# M5StickCplusbattery.net
KiCad netlist of a schematic drawn in EAGLE
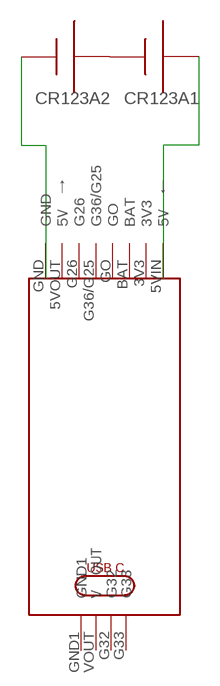
[diagram p0: schematic, sheet 1]

(export (version "E")
  (design (tool "Eeschema 10.0.6"))
  (components
    (comp (ref "CR123A1")
      (value "AAA")
      (footprint "eagle-import:12BH412")
      (libsource (lib "eagle-import") (part "AAA"))
    )
    (comp (ref "CR123A2")
      (value "AAA")
      (footprint "eagle-import:12BH412")
      (libsource (lib "eagle-import") (part "AAA"))
    )
    (comp (ref "U$1")
      (value "M5STICKCPLUS")
      (footprint "eagle-import:M5STICK")
      (libsource (lib "eagle-import") (part "M5STICKCPLUS"))
    )
  )
  (nets
    (net (code "1") (name "Net-(CR123A1-Pad+)") (class "Default")
      (node (ref "CR123A1") (pin "+") (pinfunction "+_+") (pintype "bidirectional"))
      (node (ref "CR123A2") (pin "-") (pinfunction "-_-") (pintype "bidirectional"))
    )
    (net (code "2") (name "Net-(CR123A2-Pad+)") (class "Default")
      (node (ref "CR123A2") (pin "+") (pinfunction "+_+") (pintype "bidirectional"))
      (node (ref "U$1") (pin "GND") (pinfunction "GND_GND") (pintype "bidirectional"))
    )
    (net (code "3") (name "Net-(U$1-5V　←)") (class "Default")
      (node (ref "CR123A1") (pin "-") (pinfunction "-_-") (pintype "bidirectional"))
      (node (ref "U$1") (pin "5VIN") (pinfunction "5V　←_5VIN") (pintype "bidirectional"))
    )
    (net (code "4") (name "unconnected-(U$1-5V　→-Pad5VOUT)") (class "Default")
      (node (ref "U$1") (pin "5VOUT") (pinfunction "5V　→_5VOUT") (pintype "bidirectional"))
    )
    (net (code "5") (name "unconnected-(U$1-Pad3V3)") (class "Default")
      (node (ref "U$1") (pin "3V3") (pinfunction "3V3_3V3") (pintype "bidirectional"))
    )
    (net (code "6") (name "unconnected-(U$1-PadBAT)") (class "Default")
      (node (ref "U$1") (pin "BAT") (pinfunction "BAT_BAT") (pintype "bidirectional"))
    )
    (net (code "7") (name "unconnected-(U$1-PadG26)") (class "Default")
      (node (ref "U$1") (pin "G26") (pinfunction "G26_G26") (pintype "bidirectional"))
    )
    (net (code "8") (name "unconnected-(U$1-PadG32)") (class "Default")
      (node (ref "U$1") (pin "G32") (pinfunction "G32_G32") (pintype "bidirectional"))
    )
    (net (code "9") (name "unconnected-(U$1-PadG33)") (class "Default")
      (node (ref "U$1") (pin "G33") (pinfunction "G33_G33") (pintype "bidirectional"))
    )
    (net (code "10") (name "unconnected-(U$1-PadG36{slash}G25)") (class "Default")
      (node (ref "U$1") (pin "G36/G25") (pinfunction "G36/G25_G36/G25") (pintype "bidirectional"))
    )
    (net (code "11") (name "unconnected-(U$1-PadGND1)") (class "Default")
      (node (ref "U$1") (pin "GND1") (pinfunction "GND1_GND1") (pintype "bidirectional"))
    )
    (net (code "12") (name "unconnected-(U$1-PadGO)") (class "Default")
      (node (ref "U$1") (pin "GO") (pinfunction "GO_GO") (pintype "bidirectional"))
    )
    (net (code "13") (name "unconnected-(U$1-V　OUT-PadVOUT)") (class "Default")
      (node (ref "U$1") (pin "VOUT") (pinfunction "V　OUT_VOUT") (pintype "bidirectional"))
    )
  )
)
